# RF-Shield.net
KiCad netlist of a schematic drawn in EAGLE
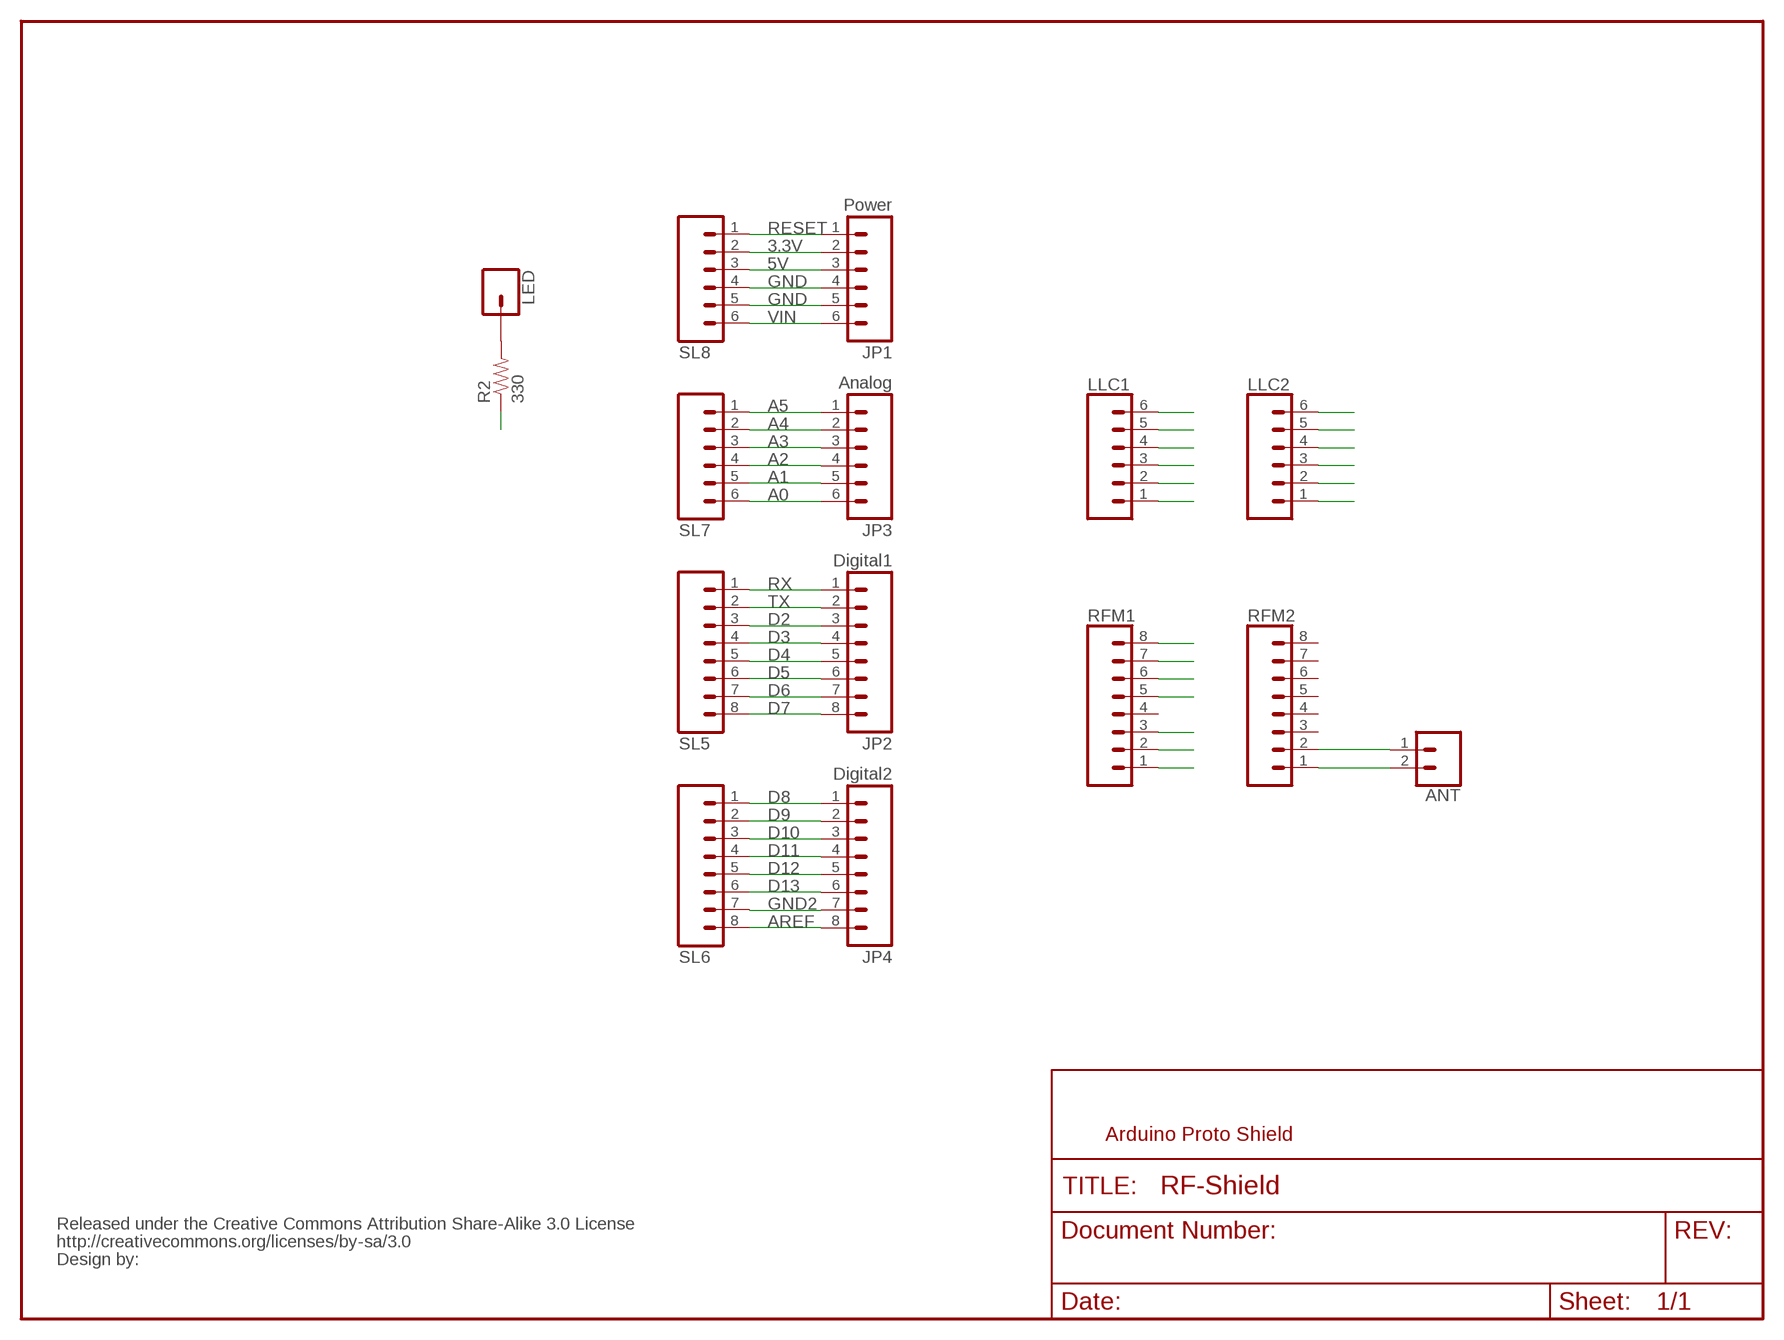
[diagram p0: schematic, sheet 1]

(export (version "E")
  (design (tool "Eeschema 10.0.6"))
  (components
    (comp (ref "ANT")
      (value "CONN_021X02_NO_SILK")
      (footprint "eagle-import:1X02_NO_SILK")
      (libsource (lib "eagle-import") (part "CONN_021X02_NO_SILK"))
    )
    (comp (ref "JP1")
      (value "Power")
      (footprint "eagle-import:1X06")
      (libsource (lib "eagle-import") (part "M06SIP"))
    )
    (comp (ref "JP2")
      (value "Digital1")
      (footprint "eagle-import:1X08")
      (libsource (lib "eagle-import") (part "M08"))
    )
    (comp (ref "JP3")
      (value "Analog")
      (footprint "eagle-import:1X06")
      (libsource (lib "eagle-import") (part "M06SIP"))
    )
    (comp (ref "JP4")
      (value "Digital2")
      (footprint "eagle-import:1X08")
      (libsource (lib "eagle-import") (part "M08"))
    )
    (comp (ref "LED")
      (value "CONN_01PTH_NO_SILK_YES_STOP")
      (footprint "eagle-import:1X01_NO_SILK")
      (libsource (lib "eagle-import") (part "CONN_01PTH_NO_SILK_YES_STOP"))
    )
    (comp (ref "LLC1")
      (value "CONN_06NO_SILK_NO_POP")
      (footprint "eagle-import:1X06_NO_SILK")
      (libsource (lib "eagle-import") (part "CONN_06NO_SILK_NO_POP"))
    )
    (comp (ref "LLC2")
      (value "CONN_06NO_SILK_NO_POP")
      (footprint "eagle-import:1X06_NO_SILK")
      (libsource (lib "eagle-import") (part "CONN_06NO_SILK_NO_POP"))
    )
    (comp (ref "R2")
      (value "330")
      (footprint "eagle-import:AXIAL-0.3")
      (libsource (lib "eagle-import") (part "RESISTORPTH1"))
    )
    (comp (ref "RFM1")
      (value "CONN_08NO_SILK_FEMALE_PTH")
      (footprint "eagle-import:1X08_NO_SILK")
      (libsource (lib "eagle-import") (part "CONN_08NO_SILK_FEMALE_PTH"))
    )
    (comp (ref "RFM2")
      (value "CONN_08NO_SILK_FEMALE_PTH")
      (footprint "eagle-import:1X08_NO_SILK")
      (libsource (lib "eagle-import") (part "CONN_08NO_SILK_FEMALE_PTH"))
    )
    (comp (ref "SL5")
      (value "M08")
      (footprint "eagle-import:1X08")
      (libsource (lib "eagle-import") (part "M08"))
    )
    (comp (ref "SL6")
      (value "M08")
      (footprint "eagle-import:1X08")
      (libsource (lib "eagle-import") (part "M08"))
    )
    (comp (ref "SL7")
      (value "M06SIP")
      (footprint "eagle-import:1X06")
      (libsource (lib "eagle-import") (part "M06SIP"))
    )
    (comp (ref "SL8")
      (value "M06SIP")
      (footprint "eagle-import:1X06")
      (libsource (lib "eagle-import") (part "M06SIP"))
    )
    (comp (ref "U$2")
      (value "CREATIVE_COMMONS")
      (footprint "eagle-import:CREATIVE_COMMONS")
      (libsource (lib "eagle-import") (part "CREATIVE_COMMONS"))
    )
  )
  (nets
    (net (code "1") (name "/3.3V") (class "Default")
      (node (ref "JP1") (pin "2") (pinfunction "2_2") (pintype "passive"))
      (node (ref "LLC2") (pin "3") (pinfunction "3_3") (pintype "passive"))
      (node (ref "RFM1") (pin "1") (pinfunction "1_1") (pintype "passive"))
      (node (ref "SL8") (pin "2") (pinfunction "2_2") (pintype "passive"))
    )
    (net (code "2") (name "/5V") (class "Default")
      (node (ref "JP1") (pin "3") (pinfunction "3_3") (pintype "passive"))
      (node (ref "LLC1") (pin "3") (pinfunction "3_3") (pintype "passive"))
      (node (ref "SL8") (pin "3") (pinfunction "3_3") (pintype "passive"))
    )
    (net (code "3") (name "/A0") (class "Default")
      (node (ref "JP3") (pin "6") (pinfunction "6_6") (pintype "passive"))
      (node (ref "SL7") (pin "6") (pinfunction "6_6") (pintype "passive"))
    )
    (net (code "4") (name "/A1") (class "Default")
      (node (ref "JP3") (pin "5") (pinfunction "5_5") (pintype "passive"))
      (node (ref "SL7") (pin "5") (pinfunction "5_5") (pintype "passive"))
    )
    (net (code "5") (name "/A2") (class "Default")
      (node (ref "JP3") (pin "4") (pinfunction "4_4") (pintype "passive"))
      (node (ref "SL7") (pin "4") (pinfunction "4_4") (pintype "passive"))
    )
    (net (code "6") (name "/A3") (class "Default")
      (node (ref "JP3") (pin "3") (pinfunction "3_3") (pintype "passive"))
      (node (ref "SL7") (pin "3") (pinfunction "3_3") (pintype "passive"))
    )
    (net (code "7") (name "/A4") (class "Default")
      (node (ref "JP3") (pin "2") (pinfunction "2_2") (pintype "passive"))
      (node (ref "SL7") (pin "2") (pinfunction "2_2") (pintype "passive"))
    )
    (net (code "8") (name "/A5") (class "Default")
      (node (ref "JP3") (pin "1") (pinfunction "1_1") (pintype "passive"))
      (node (ref "SL7") (pin "1") (pinfunction "1_1") (pintype "passive"))
    )
    (net (code "9") (name "/AREF") (class "Default")
      (node (ref "JP4") (pin "8") (pinfunction "8_8") (pintype "passive"))
      (node (ref "SL6") (pin "8") (pinfunction "8_8") (pintype "passive"))
    )
    (net (code "10") (name "/C") (class "Default")
      (node (ref "LLC2") (pin "2") (pinfunction "2_2") (pintype "passive"))
      (node (ref "RFM1") (pin "6") (pinfunction "6_6") (pintype "passive"))
    )
    (net (code "11") (name "/D2") (class "Default")
      (node (ref "JP2") (pin "3") (pinfunction "3_3") (pintype "passive"))
      (node (ref "RFM1") (pin "3") (pinfunction "3_3") (pintype "passive"))
      (node (ref "SL5") (pin "3") (pinfunction "3_3") (pintype "passive"))
    )
    (net (code "12") (name "/D3") (class "Default")
      (node (ref "JP2") (pin "4") (pinfunction "4_4") (pintype "passive"))
      (node (ref "SL5") (pin "4") (pinfunction "4_4") (pintype "passive"))
    )
    (net (code "13") (name "/D4") (class "Default")
      (node (ref "JP2") (pin "5") (pinfunction "5_5") (pintype "passive"))
      (node (ref "SL5") (pin "5") (pinfunction "5_5") (pintype "passive"))
    )
    (net (code "14") (name "/D5") (class "Default")
      (node (ref "JP2") (pin "6") (pinfunction "6_6") (pintype "passive"))
      (node (ref "SL5") (pin "6") (pinfunction "6_6") (pintype "passive"))
    )
    (net (code "15") (name "/D6") (class "Default")
      (node (ref "JP2") (pin "7") (pinfunction "7_7") (pintype "passive"))
      (node (ref "SL5") (pin "7") (pinfunction "7_7") (pintype "passive"))
    )
    (net (code "16") (name "/D7") (class "Default")
      (node (ref "JP2") (pin "8") (pinfunction "8_8") (pintype "passive"))
      (node (ref "SL5") (pin "8") (pinfunction "8_8") (pintype "passive"))
    )
    (net (code "17") (name "/D8") (class "Default")
      (node (ref "JP4") (pin "1") (pinfunction "1_1") (pintype "passive"))
      (node (ref "SL6") (pin "1") (pinfunction "1_1") (pintype "passive"))
    )
    (net (code "18") (name "/D9") (class "Default")
      (node (ref "JP4") (pin "2") (pinfunction "2_2") (pintype "passive"))
      (node (ref "SL6") (pin "2") (pinfunction "2_2") (pintype "passive"))
    )
    (net (code "19") (name "/D10") (class "Default")
      (node (ref "JP4") (pin "3") (pinfunction "3_3") (pintype "passive"))
      (node (ref "LLC1") (pin "1") (pinfunction "1_1") (pintype "passive"))
      (node (ref "SL6") (pin "3") (pinfunction "3_3") (pintype "passive"))
    )
    (net (code "20") (name "/D11") (class "Default")
      (node (ref "JP4") (pin "4") (pinfunction "4_4") (pintype "passive"))
      (node (ref "LLC1") (pin "5") (pinfunction "5_5") (pintype "passive"))
      (node (ref "SL6") (pin "4") (pinfunction "4_4") (pintype "passive"))
    )
    (net (code "21") (name "/D12") (class "Default")
      (node (ref "JP4") (pin "5") (pinfunction "5_5") (pintype "passive"))
      (node (ref "LLC1") (pin "6") (pinfunction "6_6") (pintype "passive"))
      (node (ref "SL6") (pin "5") (pinfunction "5_5") (pintype "passive"))
    )
    (net (code "22") (name "/D13") (class "Default")
      (node (ref "JP4") (pin "6") (pinfunction "6_6") (pintype "passive"))
      (node (ref "LLC1") (pin "2") (pinfunction "2_2") (pintype "passive"))
      (node (ref "SL6") (pin "6") (pinfunction "6_6") (pintype "passive"))
    )
    (net (code "23") (name "/GND") (class "Default")
      (node (ref "JP1") (pin "4") (pinfunction "4_4") (pintype "passive"))
      (node (ref "JP1") (pin "5") (pinfunction "5_5") (pintype "passive"))
      (node (ref "LLC1") (pin "4") (pinfunction "4_4") (pintype "passive"))
      (node (ref "LLC2") (pin "4") (pinfunction "4_4") (pintype "passive"))
      (node (ref "RFM1") (pin "2") (pinfunction "2_2") (pintype "passive"))
      (node (ref "SL8") (pin "4") (pinfunction "4_4") (pintype "passive"))
      (node (ref "SL8") (pin "5") (pinfunction "5_5") (pintype "passive"))
    )
    (net (code "24") (name "/GND2") (class "Default")
      (node (ref "JP4") (pin "7") (pinfunction "7_7") (pintype "passive"))
      (node (ref "R2") (pin "P$1") (pinfunction "1_P$1") (pintype "passive"))
      (node (ref "SL6") (pin "7") (pinfunction "7_7") (pintype "passive"))
    )
    (net (code "25") (name "/I") (class "Default")
      (node (ref "LLC2") (pin "5") (pinfunction "5_5") (pintype "passive"))
      (node (ref "RFM1") (pin "7") (pinfunction "7_7") (pintype "passive"))
    )
    (net (code "26") (name "/O") (class "Default")
      (node (ref "LLC2") (pin "6") (pinfunction "6_6") (pintype "passive"))
      (node (ref "RFM1") (pin "8") (pinfunction "8_8") (pintype "passive"))
    )
    (net (code "27") (name "/RESET") (class "Default")
      (node (ref "JP1") (pin "1") (pinfunction "1_1") (pintype "passive"))
      (node (ref "SL8") (pin "1") (pinfunction "1_1") (pintype "passive"))
    )
    (net (code "28") (name "/RX") (class "Default")
      (node (ref "JP2") (pin "1") (pinfunction "1_1") (pintype "passive"))
      (node (ref "SL5") (pin "1") (pinfunction "1_1") (pintype "passive"))
    )
    (net (code "29") (name "/S") (class "Default")
      (node (ref "LLC2") (pin "1") (pinfunction "1_1") (pintype "passive"))
      (node (ref "RFM1") (pin "5") (pinfunction "5_5") (pintype "passive"))
    )
    (net (code "30") (name "/TX") (class "Default")
      (node (ref "JP2") (pin "2") (pinfunction "2_2") (pintype "passive"))
      (node (ref "SL5") (pin "2") (pinfunction "2_2") (pintype "passive"))
    )
    (net (code "31") (name "/VIN") (class "Default")
      (node (ref "JP1") (pin "6") (pinfunction "6_6") (pintype "passive"))
      (node (ref "SL8") (pin "6") (pinfunction "6_6") (pintype "passive"))
    )
    (net (code "32") (name "Net-(ANT-Pad1)") (class "Default")
      (node (ref "ANT") (pin "1") (pinfunction "1_1") (pintype "passive"))
      (node (ref "RFM2") (pin "2") (pinfunction "2_2") (pintype "passive"))
    )
    (net (code "33") (name "Net-(ANT-Pad2)") (class "Default")
      (node (ref "ANT") (pin "2") (pinfunction "2_2") (pintype "passive"))
      (node (ref "RFM2") (pin "1") (pinfunction "1_1") (pintype "passive"))
    )
    (net (code "34") (name "Net-(R2-2)") (class "Default")
      (node (ref "LED") (pin "1") (pinfunction "1_1") (pintype "passive"))
      (node (ref "R2") (pin "P$2") (pinfunction "2_P$2") (pintype "passive"))
    )
    (net (code "35") (name "unconnected-(RFM1-Pad4)") (class "Default")
      (node (ref "RFM1") (pin "4") (pinfunction "4_4") (pintype "passive"))
    )
    (net (code "36") (name "unconnected-(RFM2-Pad3)") (class "Default")
      (node (ref "RFM2") (pin "3") (pinfunction "3_3") (pintype "passive"))
    )
    (net (code "37") (name "unconnected-(RFM2-Pad4)") (class "Default")
      (node (ref "RFM2") (pin "4") (pinfunction "4_4") (pintype "passive"))
    )
    (net (code "38") (name "unconnected-(RFM2-Pad5)") (class "Default")
      (node (ref "RFM2") (pin "5") (pinfunction "5_5") (pintype "passive"))
    )
    (net (code "39") (name "unconnected-(RFM2-Pad6)") (class "Default")
      (node (ref "RFM2") (pin "6") (pinfunction "6_6") (pintype "passive"))
    )
    (net (code "40") (name "unconnected-(RFM2-Pad7)") (class "Default")
      (node (ref "RFM2") (pin "7") (pinfunction "7_7") (pintype "passive"))
    )
    (net (code "41") (name "unconnected-(RFM2-Pad8)") (class "Default")
      (node (ref "RFM2") (pin "8") (pinfunction "8_8") (pintype "passive"))
    )
  )
)
